# D32_Pro_-_TFT_OneSize.net
KiCad netlist of a schematic drawn in EAGLE
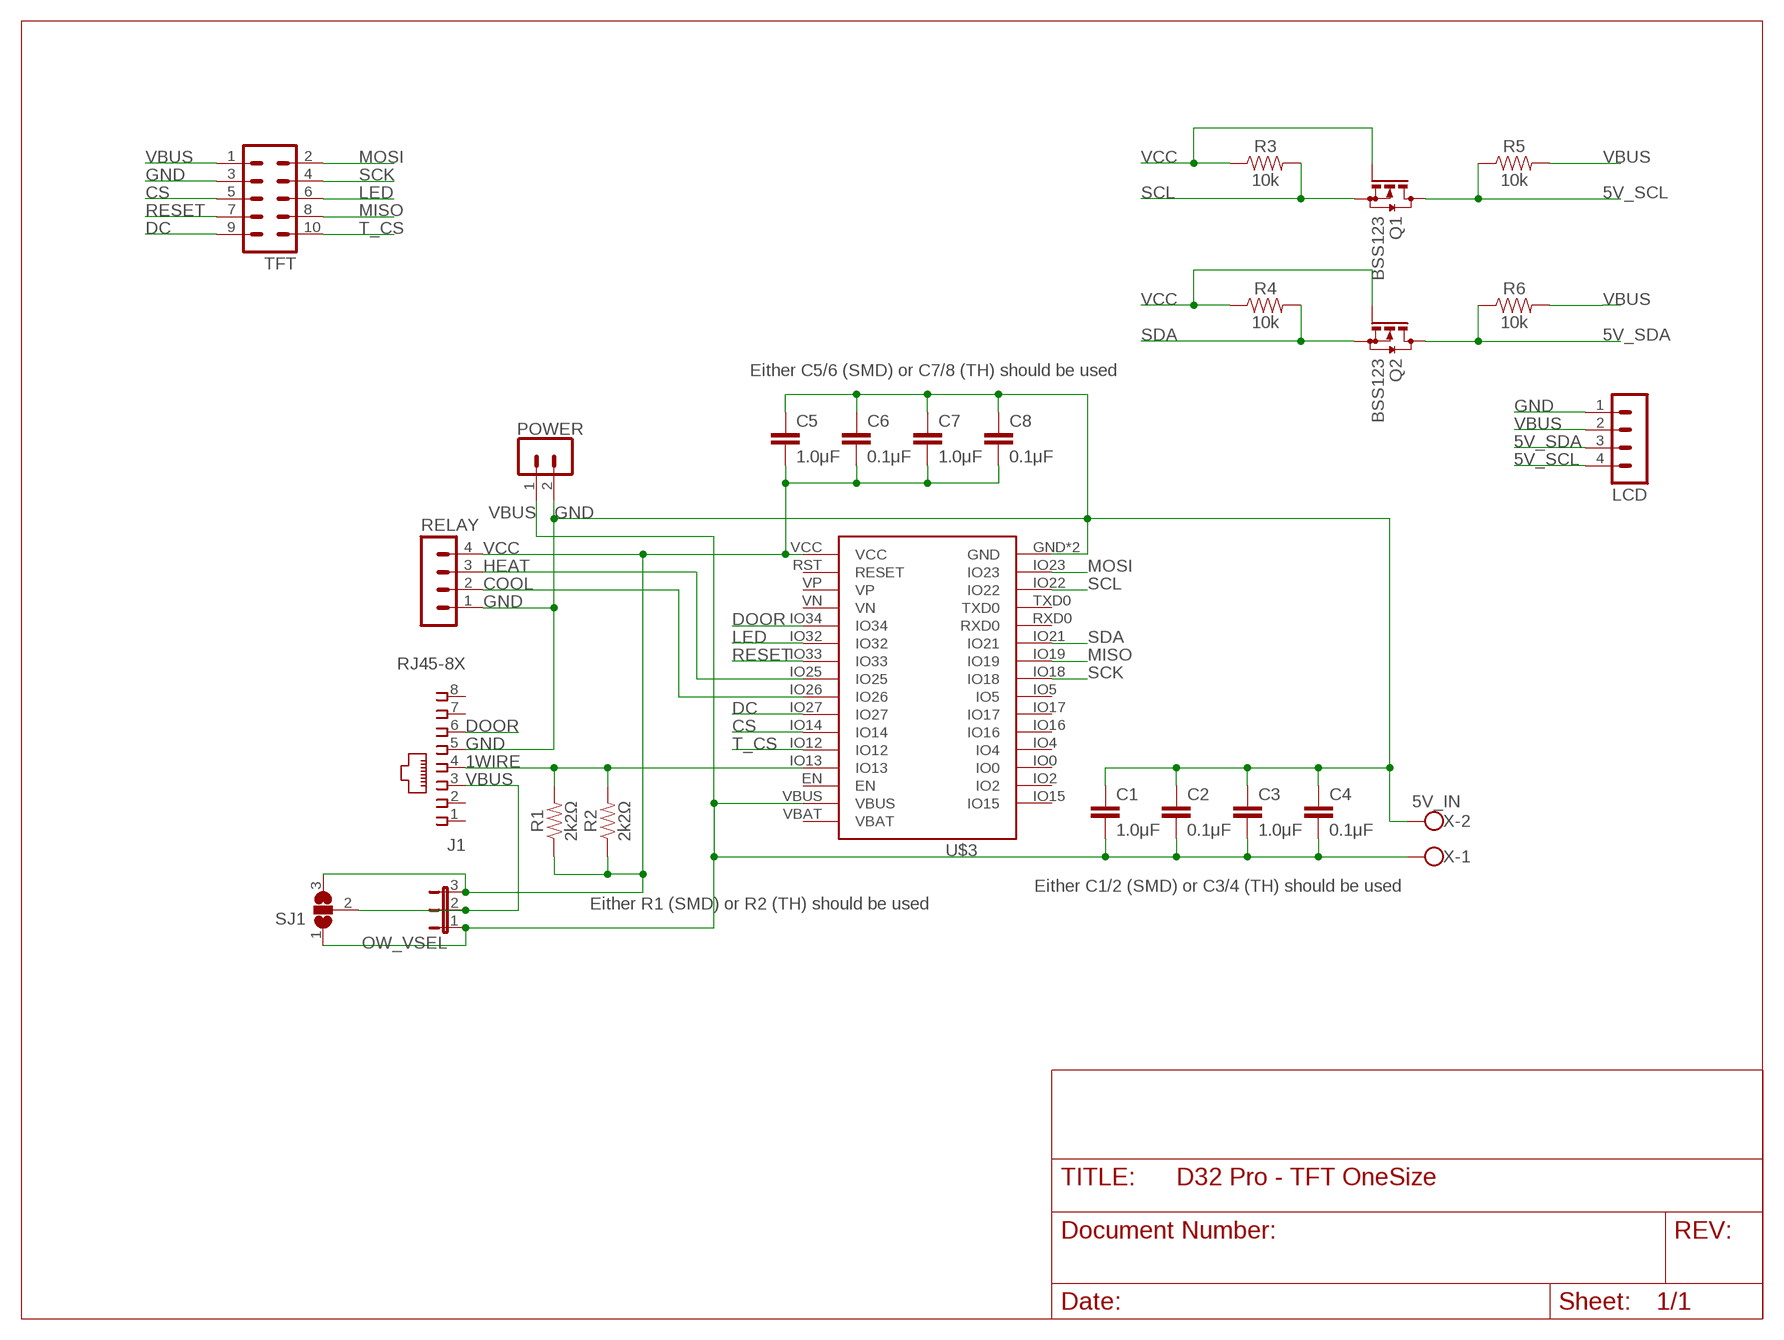
[diagram p0: schematic, sheet 1]

(export (version "E")
  (design (tool "Eeschema 10.0.6"))
  (components
    (comp (ref "C1")
      (value "1.0μF")
      (footprint "eagle-import:SMD-1206")
      (libsource (lib "eagle-import") (part "CAP_SMD1206"))
    )
    (comp (ref "C2")
      (value "0.1μF")
      (footprint "eagle-import:SMD-1206")
      (libsource (lib "eagle-import") (part "CAP_SMD1206"))
    )
    (comp (ref "C3")
      (value "1.0μF")
      (footprint "eagle-import:CAP_PTH-2.54")
      (libsource (lib "eagle-import") (part "CAP_CERAMIC_2.54"))
    )
    (comp (ref "C4")
      (value "0.1μF")
      (footprint "eagle-import:CAP_PTH-2.54")
      (libsource (lib "eagle-import") (part "CAP_CERAMIC_2.54"))
    )
    (comp (ref "C5")
      (value "1.0μF")
      (footprint "eagle-import:SMD-1206")
      (libsource (lib "eagle-import") (part "CAP_SMD1206"))
    )
    (comp (ref "C6")
      (value "0.1μF")
      (footprint "eagle-import:SMD-1206")
      (libsource (lib "eagle-import") (part "CAP_SMD1206"))
    )
    (comp (ref "C7")
      (value "1.0μF")
      (footprint "eagle-import:CAP_PTH-2.54")
      (libsource (lib "eagle-import") (part "CAP_CERAMIC_2.54"))
    )
    (comp (ref "C8")
      (value "0.1μF")
      (footprint "eagle-import:CAP_PTH-2.54")
      (libsource (lib "eagle-import") (part "CAP_CERAMIC_2.54"))
    )
    (comp (ref "J1")
      (value "RJ45-8X")
      (footprint "eagle-import:RJ45-NO-SHIELD-NOLINE")
      (libsource (lib "eagle-import") (part "RJ45-8X"))
    )
    (comp (ref "LCD")
      (value "HDR-4")
      (footprint "eagle-import:HDR-4_VERT")
      (libsource (lib "eagle-import") (part "HDR-4"))
    )
    (comp (ref "OW_VSEL")
      (value "JP2E")
      (footprint "eagle-import:JP2")
      (libsource (lib "eagle-import") (part "JP2E"))
    )
    (comp (ref "Q1")
      (value "BSS123")
      (footprint "eagle-import:SOT23")
      (libsource (lib "eagle-import") (part "BSS123"))
    )
    (comp (ref "Q2")
      (value "BSS123")
      (footprint "eagle-import:SOT23")
      (libsource (lib "eagle-import") (part "BSS123"))
    )
    (comp (ref "R1")
      (value "2k2Ω")
      (footprint "eagle-import:SMD-1206")
      (libsource (lib "eagle-import") (part "RES_SMD1206"))
    )
    (comp (ref "R2")
      (value "2k2Ω")
      (footprint "eagle-import:AXIAL-0.3")
      (libsource (lib "eagle-import") (part "1KOHM-HORIZ-1/4W-5%"))
    )
    (comp (ref "R3")
      (value "10k")
      (footprint "eagle-import:SMD-1206")
      (libsource (lib "eagle-import") (part "RES_SMD1206"))
    )
    (comp (ref "R4")
      (value "10k")
      (footprint "eagle-import:SMD-1206")
      (libsource (lib "eagle-import") (part "RES_SMD1206"))
    )
    (comp (ref "R5")
      (value "10k")
      (footprint "eagle-import:SMD-1206")
      (libsource (lib "eagle-import") (part "RES_SMD1206"))
    )
    (comp (ref "R6")
      (value "10k")
      (footprint "eagle-import:SMD-1206")
      (libsource (lib "eagle-import") (part "RES_SMD1206"))
    )
    (comp (ref "RELAY")
      (value "HDR-4")
      (footprint "eagle-import:HDR-4_VERT")
      (libsource (lib "eagle-import") (part "HDR-4"))
    )
    (comp (ref "SJ1")
      (value "SJ2WW")
      (footprint "eagle-import:SJ_2W")
      (libsource (lib "eagle-import") (part "SJ2WW"))
    )
    (comp (ref "TFT")
      (value "MA05-2")
      (footprint "eagle-import:MA05-2")
      (libsource (lib "eagle-import") (part "MA05-2"))
    )
    (comp (ref "U$3")
      (value "WEMOS-D32D32_PRO_NO-BATT")
      (footprint "eagle-import:D32_PRO_NO-BATT")
      (libsource (lib "eagle-import") (part "WEMOS-D32D32_PRO_NO-BATT"))
    )
    (comp (ref "U$5")
      (value "POWER")
      (footprint "eagle-import:HDR-2_VERT")
      (libsource (lib "eagle-import") (part "HDR-2"))
    )
    (comp (ref "X")
      (value "5V_IN")
      (footprint "eagle-import:W237-102")
      (fields (field (name "MPN") "237-102"))
      (libsource (lib "eagle-import") (part "W237-102"))
    )
  )
  (nets
    (net (code "1") (name "/1WIRE") (class "Default")
      (node (ref "J1") (pin "4") (pinfunction "4_4") (pintype "passive"))
      (node (ref "R1") (pin "2") (pinfunction "2_2") (pintype "passive"))
      (node (ref "R2") (pin "P$2") (pinfunction "2_P$2") (pintype "passive"))
      (node (ref "U$3") (pin "IO13") (pinfunction "IO13_IO13") (pintype "bidirectional"))
    )
    (net (code "2") (name "/5V_SCL") (class "Default")
      (node (ref "LCD") (pin "4") (pinfunction "4_4") (pintype "passive"))
      (node (ref "Q1") (pin "3") (pinfunction "D_3") (pintype "passive"))
      (node (ref "R5") (pin "1") (pinfunction "1_1") (pintype "passive"))
    )
    (net (code "3") (name "/5V_SDA") (class "Default")
      (node (ref "LCD") (pin "3") (pinfunction "3_3") (pintype "passive"))
      (node (ref "Q2") (pin "3") (pinfunction "D_3") (pintype "passive"))
      (node (ref "R6") (pin "1") (pinfunction "1_1") (pintype "passive"))
    )
    (net (code "4") (name "/COOL") (class "Default")
      (node (ref "RELAY") (pin "2") (pinfunction "2_2") (pintype "passive"))
      (node (ref "U$3") (pin "IO26") (pinfunction "IO26_IO26") (pintype "bidirectional"))
    )
    (net (code "5") (name "/CS") (class "Default")
      (node (ref "TFT") (pin "5") (pinfunction "5_5") (pintype "passive"))
      (node (ref "U$3") (pin "IO14") (pinfunction "IO14_IO14") (pintype "bidirectional"))
    )
    (net (code "6") (name "/DC") (class "Default")
      (node (ref "TFT") (pin "9") (pinfunction "9_9") (pintype "passive"))
      (node (ref "U$3") (pin "IO27") (pinfunction "IO27_IO27") (pintype "bidirectional"))
    )
    (net (code "7") (name "/DOOR") (class "Default")
      (node (ref "J1") (pin "6") (pinfunction "6_6") (pintype "passive"))
      (node (ref "U$3") (pin "IO34") (pinfunction "IO34_IO34") (pintype "bidirectional"))
    )
    (net (code "8") (name "/GND") (class "Default")
      (node (ref "C1") (pin "1") (pinfunction "1_1") (pintype "passive"))
      (node (ref "C2") (pin "1") (pinfunction "1_1") (pintype "passive"))
      (node (ref "C3") (pin "1") (pinfunction "1_1") (pintype "passive"))
      (node (ref "C4") (pin "1") (pinfunction "1_1") (pintype "passive"))
      (node (ref "C5") (pin "1") (pinfunction "1_1") (pintype "passive"))
      (node (ref "C6") (pin "1") (pinfunction "1_1") (pintype "passive"))
      (node (ref "C7") (pin "1") (pinfunction "1_1") (pintype "passive"))
      (node (ref "C8") (pin "1") (pinfunction "1_1") (pintype "passive"))
      (node (ref "J1") (pin "5") (pinfunction "5_5") (pintype "passive"))
      (node (ref "LCD") (pin "1") (pinfunction "1_1") (pintype "passive"))
      (node (ref "RELAY") (pin "1") (pinfunction "1_1") (pintype "passive"))
      (node (ref "TFT") (pin "3") (pinfunction "3_3") (pintype "passive"))
      (node (ref "U$3") (pin "GND") (pinfunction "GND_GND") (pintype "power_in"))
      (node (ref "U$3") (pin "GND2") (pinfunction "GND_GND2") (pintype "power_in"))
      (node (ref "U$5") (pin "2") (pinfunction "2_2") (pintype "passive"))
      (node (ref "X") (pin "2") (pinfunction "KL_2") (pintype "passive"))
    )
    (net (code "9") (name "/HEAT") (class "Default")
      (node (ref "RELAY") (pin "3") (pinfunction "3_3") (pintype "passive"))
      (node (ref "U$3") (pin "IO25") (pinfunction "IO25_IO25") (pintype "bidirectional"))
    )
    (net (code "10") (name "/LED") (class "Default")
      (node (ref "TFT") (pin "6") (pinfunction "6_6") (pintype "passive"))
      (node (ref "U$3") (pin "IO32") (pinfunction "IO32_IO32") (pintype "bidirectional"))
    )
    (net (code "11") (name "/MISO") (class "Default")
      (node (ref "TFT") (pin "8") (pinfunction "8_8") (pintype "passive"))
      (node (ref "U$3") (pin "IO19") (pinfunction "IO19_IO19") (pintype "bidirectional"))
    )
    (net (code "12") (name "/MOSI") (class "Default")
      (node (ref "TFT") (pin "2") (pinfunction "2_2") (pintype "passive"))
      (node (ref "U$3") (pin "IO23") (pinfunction "IO23_IO23") (pintype "bidirectional"))
    )
    (net (code "13") (name "/RESET") (class "Default")
      (node (ref "TFT") (pin "7") (pinfunction "7_7") (pintype "passive"))
      (node (ref "U$3") (pin "IO33") (pinfunction "IO33_IO33") (pintype "bidirectional"))
    )
    (net (code "14") (name "/SCK") (class "Default")
      (node (ref "TFT") (pin "4") (pinfunction "4_4") (pintype "passive"))
      (node (ref "U$3") (pin "IO18") (pinfunction "IO18_IO18") (pintype "bidirectional"))
    )
    (net (code "15") (name "/SCL") (class "Default")
      (node (ref "Q1") (pin "2") (pinfunction "S_2") (pintype "passive"))
      (node (ref "R3") (pin "2") (pinfunction "2_2") (pintype "passive"))
      (node (ref "U$3") (pin "IO22") (pinfunction "IO22_IO22") (pintype "bidirectional"))
    )
    (net (code "16") (name "/SDA") (class "Default")
      (node (ref "Q2") (pin "2") (pinfunction "S_2") (pintype "passive"))
      (node (ref "R4") (pin "2") (pinfunction "2_2") (pintype "passive"))
      (node (ref "U$3") (pin "IO21") (pinfunction "IO21_IO21") (pintype "bidirectional"))
    )
    (net (code "17") (name "/T_CS") (class "Default")
      (node (ref "TFT") (pin "10") (pinfunction "10_10") (pintype "passive"))
      (node (ref "U$3") (pin "IO12") (pinfunction "IO12_IO12") (pintype "bidirectional"))
    )
    (net (code "18") (name "/VBUS") (class "Default")
      (node (ref "C1") (pin "2") (pinfunction "2_2") (pintype "passive"))
      (node (ref "C2") (pin "2") (pinfunction "2_2") (pintype "passive"))
      (node (ref "C3") (pin "2") (pinfunction "2_2") (pintype "passive"))
      (node (ref "C4") (pin "2") (pinfunction "2_2") (pintype "passive"))
      (node (ref "LCD") (pin "2") (pinfunction "2_2") (pintype "passive"))
      (node (ref "OW_VSEL") (pin "1") (pinfunction "1_1") (pintype "passive"))
      (node (ref "R5") (pin "2") (pinfunction "2_2") (pintype "passive"))
      (node (ref "R6") (pin "2") (pinfunction "2_2") (pintype "passive"))
      (node (ref "SJ1") (pin "1") (pinfunction "1_1") (pintype "passive"))
      (node (ref "TFT") (pin "1") (pinfunction "1_1") (pintype "passive"))
      (node (ref "U$3") (pin "VBUS") (pinfunction "VBUS_VBUS") (pintype "bidirectional"))
      (node (ref "U$5") (pin "1") (pinfunction "1_1") (pintype "passive"))
      (node (ref "X") (pin "1") (pinfunction "KL_1") (pintype "passive"))
    )
    (net (code "19") (name "/VCC") (class "Default")
      (node (ref "C5") (pin "2") (pinfunction "2_2") (pintype "passive"))
      (node (ref "C6") (pin "2") (pinfunction "2_2") (pintype "passive"))
      (node (ref "C7") (pin "2") (pinfunction "2_2") (pintype "passive"))
      (node (ref "C8") (pin "2") (pinfunction "2_2") (pintype "passive"))
      (node (ref "OW_VSEL") (pin "3") (pinfunction "3_3") (pintype "passive"))
      (node (ref "Q1") (pin "1") (pinfunction "G_1") (pintype "passive"))
      (node (ref "Q2") (pin "1") (pinfunction "G_1") (pintype "passive"))
      (node (ref "R1") (pin "1") (pinfunction "1_1") (pintype "passive"))
      (node (ref "R2") (pin "P$1") (pinfunction "1_P$1") (pintype "passive"))
      (node (ref "R3") (pin "1") (pinfunction "1_1") (pintype "passive"))
      (node (ref "R4") (pin "1") (pinfunction "1_1") (pintype "passive"))
      (node (ref "RELAY") (pin "4") (pinfunction "4_4") (pintype "passive"))
      (node (ref "SJ1") (pin "3") (pinfunction "3_3") (pintype "passive"))
      (node (ref "U$3") (pin "VCC") (pinfunction "VCC_VCC") (pintype "power_in"))
    )
    (net (code "20") (name "Net-(J1-Pad3)") (class "Default")
      (node (ref "J1") (pin "3") (pinfunction "3_3") (pintype "passive"))
      (node (ref "OW_VSEL") (pin "2") (pinfunction "2_2") (pintype "passive"))
      (node (ref "SJ1") (pin "2") (pinfunction "2_2") (pintype "passive"))
    )
    (net (code "21") (name "unconnected-(J1-Pad1)") (class "Default")
      (node (ref "J1") (pin "1") (pinfunction "1_1") (pintype "passive"))
    )
    (net (code "22") (name "unconnected-(J1-Pad2)") (class "Default")
      (node (ref "J1") (pin "2") (pinfunction "2_2") (pintype "passive"))
    )
    (net (code "23") (name "unconnected-(J1-Pad7)") (class "Default")
      (node (ref "J1") (pin "7") (pinfunction "7_7") (pintype "passive"))
    )
    (net (code "24") (name "unconnected-(J1-Pad8)") (class "Default")
      (node (ref "J1") (pin "8") (pinfunction "8_8") (pintype "passive"))
    )
    (net (code "25") (name "unconnected-(U$3-PadEN)") (class "Default")
      (node (ref "U$3") (pin "EN") (pinfunction "EN_EN") (pintype "bidirectional"))
    )
    (net (code "26") (name "unconnected-(U$3-PadIO0)") (class "Default")
      (node (ref "U$3") (pin "IO0") (pinfunction "IO0_IO0") (pintype "bidirectional"))
    )
    (net (code "27") (name "unconnected-(U$3-PadIO2)") (class "Default")
      (node (ref "U$3") (pin "IO2") (pinfunction "IO2_IO2") (pintype "bidirectional"))
    )
    (net (code "28") (name "unconnected-(U$3-PadIO4)") (class "Default")
      (node (ref "U$3") (pin "IO4") (pinfunction "IO4_IO4") (pintype "bidirectional"))
    )
    (net (code "29") (name "unconnected-(U$3-PadIO5)") (class "Default")
      (node (ref "U$3") (pin "IO5") (pinfunction "IO5_IO5") (pintype "bidirectional"))
    )
    (net (code "30") (name "unconnected-(U$3-PadIO15)") (class "Default")
      (node (ref "U$3") (pin "IO15") (pinfunction "IO15_IO15") (pintype "bidirectional"))
    )
    (net (code "31") (name "unconnected-(U$3-PadIO16)") (class "Default")
      (node (ref "U$3") (pin "IO16") (pinfunction "IO16_IO16") (pintype "bidirectional"))
    )
    (net (code "32") (name "unconnected-(U$3-PadIO17)") (class "Default")
      (node (ref "U$3") (pin "IO17") (pinfunction "IO17_IO17") (pintype "bidirectional"))
    )
    (net (code "33") (name "unconnected-(U$3-PadRXD0)") (class "Default")
      (node (ref "U$3") (pin "RXD0") (pinfunction "RXD0_RXD0") (pintype "input"))
    )
    (net (code "34") (name "unconnected-(U$3-PadTXD0)") (class "Default")
      (node (ref "U$3") (pin "TXD0") (pinfunction "TXD0_TXD0") (pintype "output"))
    )
    (net (code "35") (name "unconnected-(U$3-PadVBAT)") (class "Default")
      (node (ref "U$3") (pin "VBAT") (pinfunction "VBAT_VBAT") (pintype "bidirectional"))
    )
    (net (code "36") (name "unconnected-(U$3-PadVN)") (class "Default")
      (node (ref "U$3") (pin "VN") (pinfunction "VN_VN") (pintype "bidirectional"))
    )
    (net (code "37") (name "unconnected-(U$3-PadVP)") (class "Default")
      (node (ref "U$3") (pin "VP") (pinfunction "VP_VP") (pintype "bidirectional"))
    )
    (net (code "38") (name "unconnected-(U$3-RESET-PadRST)") (class "Default")
      (node (ref "U$3") (pin "RST") (pinfunction "RESET_RST") (pintype "bidirectional"))
    )
  )
)
